# HX711_load_cell_amplifier.net
KiCad netlist of a schematic drawn in Altium Designer
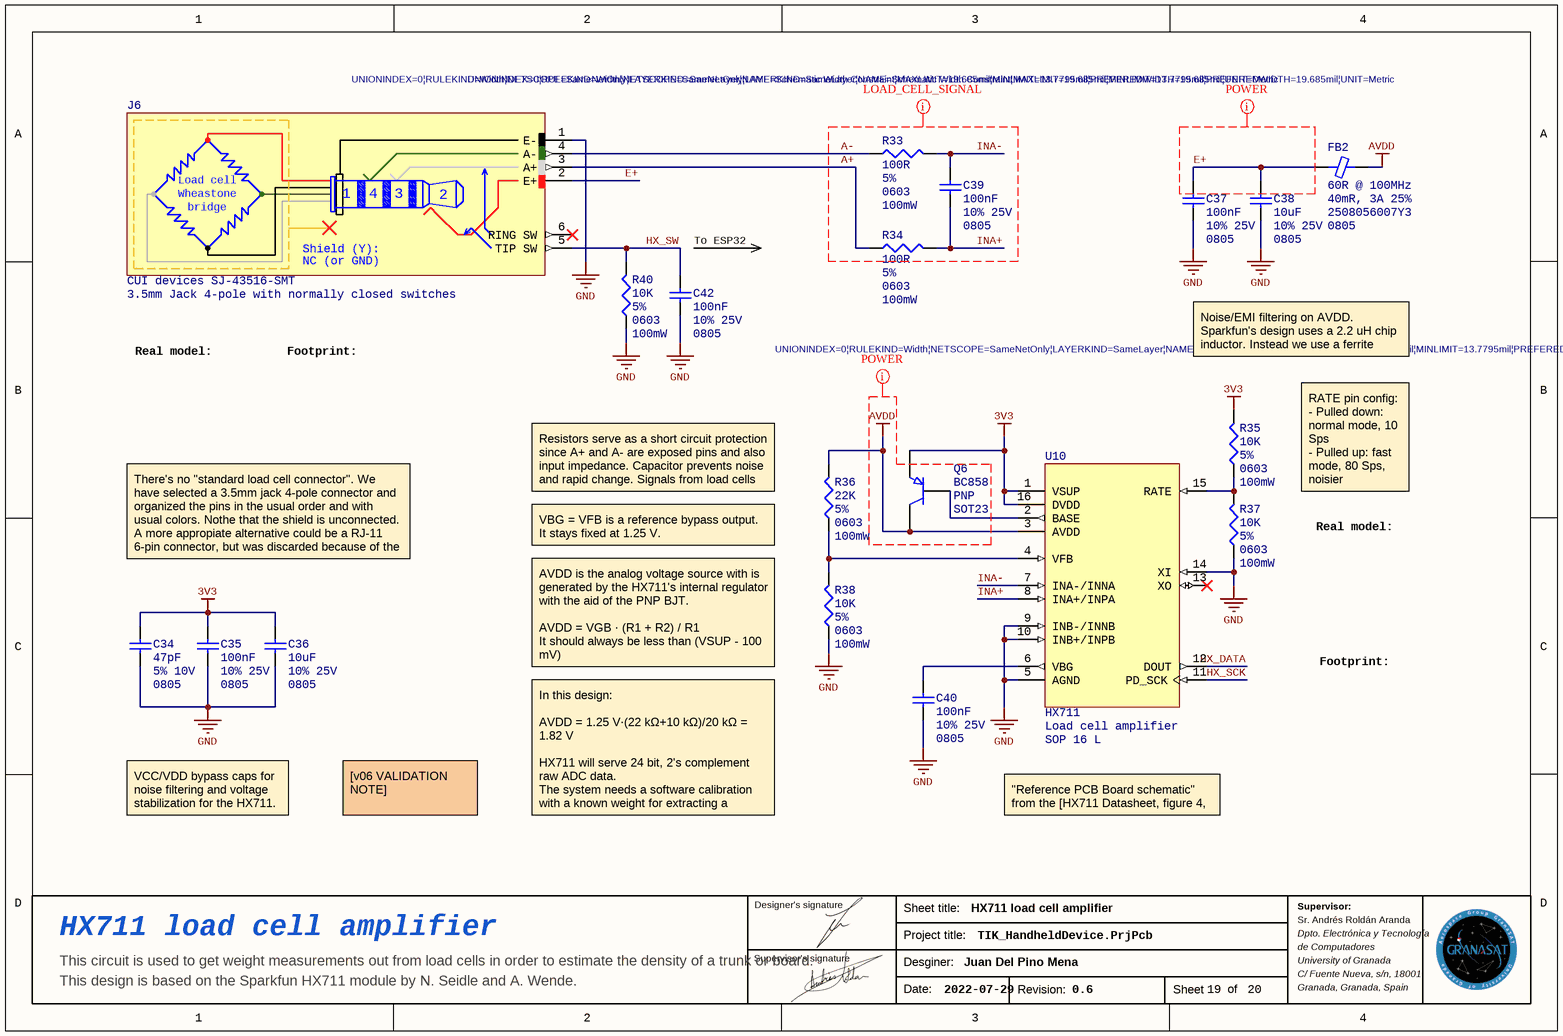
[diagram p0: HX711_load_cell_amplifier.SchDoc]

(export (version "E")
  (design (tool "Eeschema 10.0.6"))
  (components
    (comp (ref "C34")
      (value "47pF")
      (footprint "CAP 0805_2012")
      (description "Ceramic cap size 0805")
      (fields
        (field (name "TOLERANCE") "5% 10V")
        (field (name "PACKAGEDESCRIPTION") "0805")
        (field (name "Comment") "Cap_cer_0805")
      )
      (libsource (lib "tik_handheld_schlib") (part "Cap_cer_0805_47pF_5%"))
    )
    (comp (ref "C35")
      (value "100nF")
      (footprint "CAP 0805_2012")
      (description "Ceramic cap size 0805")
      (fields
        (field (name "TOLERANCE") "10% 25V")
        (field (name "PACKAGEDESCRIPTION") "0805")
        (field (name "Comment") "Cap_cer_0805")
      )
      (libsource (lib "tik_handheld_schlib") (part "Cap_cer_0805_100nF_10%"))
    )
    (comp (ref "C36")
      (value "10uF")
      (footprint "CAP 0805_2012")
      (description "Ceramic cap size 0805")
      (fields
        (field (name "TOLERANCE") "10% 25V")
        (field (name "PACKAGEDESCRIPTION") "0805")
        (field (name "Comment") "Cap_cer_0805")
      )
      (libsource (lib "tik_handheld_schlib") (part "Cap_cer_0805_10uF_10%"))
    )
    (comp (ref "C37")
      (value "100nF")
      (footprint "CAP 0805_2012")
      (description "Ceramic cap size 0805")
      (fields
        (field (name "TOLERANCE") "10% 25V")
        (field (name "PACKAGEDESCRIPTION") "0805")
        (field (name "Comment") "Cap_cer_0805")
      )
      (libsource (lib "tik_handheld_schlib") (part "Cap_cer_0805_100nF_10%"))
    )
    (comp (ref "C38")
      (value "10uF")
      (footprint "CAP 0805_2012")
      (description "Ceramic cap size 0805")
      (fields
        (field (name "TOLERANCE") "10% 25V")
        (field (name "PACKAGEDESCRIPTION") "0805")
        (field (name "Comment") "Cap_cer_0805")
      )
      (libsource (lib "tik_handheld_schlib") (part "Cap_cer_0805_10uF_10%"))
    )
    (comp (ref "C39")
      (value "100nF")
      (footprint "CAP 0805_2012")
      (description "Ceramic cap size 0805")
      (fields
        (field (name "TOLERANCE") "10% 25V")
        (field (name "PACKAGEDESCRIPTION") "0805")
        (field (name "Comment") "Cap_cer_0805")
      )
      (libsource (lib "tik_handheld_schlib") (part "Cap_cer_0805_100nF_10%"))
    )
    (comp (ref "C40")
      (value "100nF")
      (footprint "CAP 0805_2012")
      (description "Ceramic cap size 0805")
      (fields
        (field (name "TOLERANCE") "10% 25V")
        (field (name "PACKAGEDESCRIPTION") "0805")
        (field (name "Comment") "Cap_cer_0805")
      )
      (libsource (lib "tik_handheld_schlib") (part "Cap_cer_0805_100nF_10%"))
    )
    (comp (ref "C42")
      (value "100nF")
      (footprint "CAP 0805_2012")
      (description "Ceramic cap size 0805")
      (fields
        (field (name "TOLERANCE") "10% 25V")
        (field (name "PACKAGEDESCRIPTION") "0805")
        (field (name "Comment") "Cap_cer_0805")
      )
      (libsource (lib "tik_handheld_schlib") (part "Cap_cer_0805_100nF_10%"))
    )
    (comp (ref "FB2")
      (value "40mR, 3A 25%")
      (footprint "FER 0805_2012")
      (description "0805, 60Ω, 3A, 25% SMT")
      (fields
        (field (name "DESC") "60R @ 100MHz")
        (field (name "PART") "2508056007Y3")
        (field (name "PACKAGEDESCRIPTION") "0805")
        (field (name "Comment") "Ferrite Bead Chip Fair-Rite 2508056007Y3")
      )
      (libsource (lib "tik_handheld_schlib") (part "Ferrite Bead Chip Fair-Rite 2508056007Y3"))
    )
    (comp (ref "J6")
      (value "CON LOAD CELL PORT JACK")
      (footprint "JACK_6_CONN_CUI_DEVICES_SJ-43516-SMT")
      (description "3.5mm Jack 4-pole with normally closed switches")
      (fields
        (field (name "PACKAGEDESCRIPTION") "3.5mm Jack 4-pole with normally closed switches")
        (field (name "PART") "CUI devices SJ-43516-SMT")
      )
      (libsource (lib "tik_handheld_schlib") (part "CON LOAD CELL PORT JACK"))
    )
    (comp (ref "Q6")
      (value "PNP BJT BC858 transistor")
      (footprint "SOT-23-3 TO-236AB BC858")
      (description "65 V, 100 mA PNP general-purpose transistor")
      (fields
        (field (name "PART") "BC858")
        (field (name "TYPE") "PNP")
        (field (name "PACKAGEDESCRIPTION") "SOT23")
      )
      (libsource (lib "tik_handheld_schlib") (part "PNP BJT BC858 transistor"))
    )
    (comp (ref "R33")
      (value "100R")
      (footprint "RES 0603_1608")
      (description "Res size 0603 SMD mounting, low power")
      (fields
        (field (name "TOLERANCE") "5%")
        (field (name "PACKAGEDESCRIPTION") "0603")
        (field (name "POWERDISIPATED") "100mW")
        (field (name "Comment") "Res_0603_100R_5%_100mW")
      )
      (libsource (lib "tik_handheld_schlib") (part "Res_0603_100R_5%_100mW"))
    )
    (comp (ref "R34")
      (value "100R")
      (footprint "RES 0603_1608")
      (description "Res size 0603 SMD mounting, low power")
      (fields
        (field (name "TOLERANCE") "5%")
        (field (name "PACKAGEDESCRIPTION") "0603")
        (field (name "POWERDISIPATED") "100mW")
        (field (name "Comment") "Res_0603_100R_5%_100mW")
      )
      (libsource (lib "tik_handheld_schlib") (part "Res_0603_100R_5%_100mW"))
    )
    (comp (ref "R35")
      (value "10K")
      (footprint "RES 0603_1608")
      (description "Res size 0603 SMD mounting, low power")
      (fields
        (field (name "TOLERANCE") "5%")
        (field (name "PACKAGEDESCRIPTION") "0603")
        (field (name "POWERDISIPATED") "100mW")
        (field (name "Comment") "Res_0603_10K_5%_100mW_1")
      )
      (libsource (lib "tik_handheld_schlib") (part "Res_0603_10K_5%_100mW_1"))
    )
    (comp (ref "R36")
      (value "22K")
      (footprint "RES 0603_1608")
      (description "Res size 0603 SMD mounting, low power")
      (fields
        (field (name "TOLERANCE") "5%")
        (field (name "PACKAGEDESCRIPTION") "0603")
        (field (name "POWERDISIPATED") "100mW")
        (field (name "Comment") "Res_0603_22K_5%_100mW")
      )
      (libsource (lib "tik_handheld_schlib") (part "Res_0603_22K_5%_100mW"))
    )
    (comp (ref "R37")
      (value "10K")
      (footprint "RES 0603_1608")
      (description "Res size 0603 SMD mounting, low power")
      (fields
        (field (name "TOLERANCE") "5%")
        (field (name "PACKAGEDESCRIPTION") "0603")
        (field (name "POWERDISIPATED") "100mW")
        (field (name "Comment") "Res_0603_10K_5%_100mW_1")
      )
      (libsource (lib "tik_handheld_schlib") (part "Res_0603_10K_5%_100mW_1"))
    )
    (comp (ref "R38")
      (value "10K")
      (footprint "RES 0603_1608")
      (description "Res size 0603 SMD mounting, low power")
      (fields
        (field (name "TOLERANCE") "5%")
        (field (name "PACKAGEDESCRIPTION") "0603")
        (field (name "POWERDISIPATED") "100mW")
        (field (name "Comment") "Res_0603_10K_5%_100mW_1")
      )
      (libsource (lib "tik_handheld_schlib") (part "Res_0603_10K_5%_100mW_1"))
    )
    (comp (ref "R40")
      (value "10K")
      (footprint "RES 0603_1608")
      (description "Res size 0603 SMD mounting, low power")
      (fields
        (field (name "TOLERANCE") "5%")
        (field (name "PACKAGEDESCRIPTION") "0603")
        (field (name "POWERDISIPATED") "100mW")
        (field (name "Comment") "Res_0603_10K_5%_100mW_1")
      )
      (libsource (lib "tik_handheld_schlib") (part "Res_0603_10K_5%_100mW_1"))
    )
    (comp (ref "U10")
      (value "IC HX711 load cell amp")
      (footprint "SOP-16 L HX711")
      (description "HX711 load cell amplifier")
      (fields
        (field (name "PART") "HX711")
        (field (name "DESC") "Load cell amplifier")
        (field (name "PACKAGEDESCRIPTION") "SOP 16 L")
      )
      (libsource (lib "tik_handheld_schlib") (part "IC HX711 load cell amp"))
    )
  )
  (nets
    (net (code "1") (name "/A+") (class "Default")
      (node (ref "J6") (pin "3") (pinfunction "A+_3") (pintype "output"))
      (node (ref "R34") (pin "1") (pinfunction "1_1") (pintype "passive"))
    )
    (net (code "2") (name "/A-") (class "Default")
      (node (ref "J6") (pin "4") (pinfunction "A-_4") (pintype "output"))
      (node (ref "R33") (pin "1") (pinfunction "1_1") (pintype "passive"))
    )
    (net (code "3") (name "/E+") (class "Default")
      (node (ref "C37") (pin "2") (pinfunction "2_2") (pintype "passive"))
      (node (ref "C38") (pin "2") (pinfunction "2_2") (pintype "passive"))
      (node (ref "FB2") (pin "1") (pinfunction "1_1") (pintype "passive"))
      (node (ref "J6") (pin "2") (pinfunction "E+_2") (pintype "power_in"))
    )
    (net (code "4") (name "/HX_DATA") (class "Default")
      (node (ref "U10") (pin "12") (pinfunction "DOUT_12") (pintype "output"))
    )
    (net (code "5") (name "/HX_SCK") (class "Default")
      (node (ref "U10") (pin "11") (pinfunction "PD_SCK_11") (pintype "input"))
    )
    (net (code "6") (name "/HX_SW") (class "Default")
      (node (ref "C42") (pin "2") (pinfunction "2_2") (pintype "passive"))
      (node (ref "J6") (pin "5") (pinfunction "TIP_SW_5") (pintype "output"))
      (node (ref "R40") (pin "2") (pinfunction "2_2") (pintype "passive"))
    )
    (net (code "7") (name "/INA+") (class "Default")
      (node (ref "C39") (pin "1") (pinfunction "1_1") (pintype "passive"))
      (node (ref "R34") (pin "2") (pinfunction "2_2") (pintype "passive"))
      (node (ref "U10") (pin "8") (pinfunction "INA+/INPA_8") (pintype "input"))
    )
    (net (code "8") (name "/INA-") (class "Default")
      (node (ref "C39") (pin "2") (pinfunction "2_2") (pintype "passive"))
      (node (ref "R33") (pin "2") (pinfunction "2_2") (pintype "passive"))
      (node (ref "U10") (pin "7") (pinfunction "INA-/INNA_7") (pintype "input"))
    )
    (net (code "9") (name "3V3") (class "Default")
      (node (ref "C34") (pin "2") (pinfunction "2_2") (pintype "passive"))
      (node (ref "C35") (pin "2") (pinfunction "2_2") (pintype "passive"))
      (node (ref "C36") (pin "2") (pinfunction "2_2") (pintype "passive"))
      (node (ref "Q6") (pin "2") (pinfunction "E_2") (pintype "passive"))
      (node (ref "R35") (pin "2") (pinfunction "2_2") (pintype "passive"))
      (node (ref "U10") (pin "1") (pinfunction "VSUP_1") (pintype "power_in"))
      (node (ref "U10") (pin "16") (pinfunction "DVDD_16") (pintype "power_in"))
    )
    (net (code "10") (name "AVDD") (class "Default")
      (node (ref "FB2") (pin "2") (pinfunction "2_2") (pintype "passive"))
      (node (ref "Q6") (pin "3") (pinfunction "C_3") (pintype "passive"))
      (node (ref "R36") (pin "2") (pinfunction "2_2") (pintype "passive"))
      (node (ref "U10") (pin "3") (pinfunction "AVDD_3") (pintype "power_in"))
    )
    (net (code "11") (name "GND") (class "Default")
      (node (ref "C34") (pin "1") (pinfunction "1_1") (pintype "passive"))
      (node (ref "C35") (pin "1") (pinfunction "1_1") (pintype "passive"))
      (node (ref "C36") (pin "1") (pinfunction "1_1") (pintype "passive"))
      (node (ref "C37") (pin "1") (pinfunction "1_1") (pintype "passive"))
      (node (ref "C38") (pin "1") (pinfunction "1_1") (pintype "passive"))
      (node (ref "C40") (pin "1") (pinfunction "1_1") (pintype "passive"))
      (node (ref "C42") (pin "1") (pinfunction "1_1") (pintype "passive"))
      (node (ref "J6") (pin "1") (pinfunction "E-_1") (pintype "power_in"))
      (node (ref "R37") (pin "1") (pinfunction "1_1") (pintype "passive"))
      (node (ref "R38") (pin "1") (pinfunction "1_1") (pintype "passive"))
      (node (ref "R40") (pin "1") (pinfunction "1_1") (pintype "passive"))
      (node (ref "U10") (pin "10") (pinfunction "INB+/INPB_10") (pintype "input"))
      (node (ref "U10") (pin "14") (pinfunction "XI_14") (pintype "input"))
      (node (ref "U10") (pin "5") (pinfunction "AGND_5") (pintype "power_in"))
      (node (ref "U10") (pin "9") (pinfunction "INB-/INNB_9") (pintype "input"))
    )
    (net (code "12") (name "Net-(Q6-B)") (class "Default")
      (node (ref "Q6") (pin "1") (pinfunction "B_1") (pintype "passive"))
      (node (ref "U10") (pin "2") (pinfunction "BASE_2") (pintype "output"))
    )
    (net (code "13") (name "Net-(U10-RATE)") (class "Default")
      (node (ref "R35") (pin "1") (pinfunction "1_1") (pintype "passive"))
      (node (ref "R37") (pin "2") (pinfunction "2_2") (pintype "passive"))
      (node (ref "U10") (pin "15") (pinfunction "RATE_15") (pintype "input"))
    )
    (net (code "14") (name "Net-(U10-VBG)") (class "Default")
      (node (ref "C40") (pin "2") (pinfunction "2_2") (pintype "passive"))
      (node (ref "U10") (pin "6") (pinfunction "VBG_6") (pintype "output"))
    )
    (net (code "15") (name "Net-(U10-VFB)") (class "Default")
      (node (ref "R36") (pin "1") (pinfunction "1_1") (pintype "passive"))
      (node (ref "R38") (pin "2") (pinfunction "2_2") (pintype "passive"))
      (node (ref "U10") (pin "4") (pinfunction "VFB_4") (pintype "input"))
    )
    (net (code "16") (name "unconnected-(J6-RING_SW-Pad6)") (class "Default")
      (node (ref "J6") (pin "6") (pinfunction "RING_SW_6") (pintype "output+no_connect"))
    )
    (net (code "17") (name "unconnected-(U10-XO-Pad13)") (class "Default")
      (node (ref "U10") (pin "13") (pinfunction "XO_13") (pintype "bidirectional+no_connect"))
    )
  )
)
